# SineWaveGen.net
KiCad netlist of a schematic drawn in EAGLE
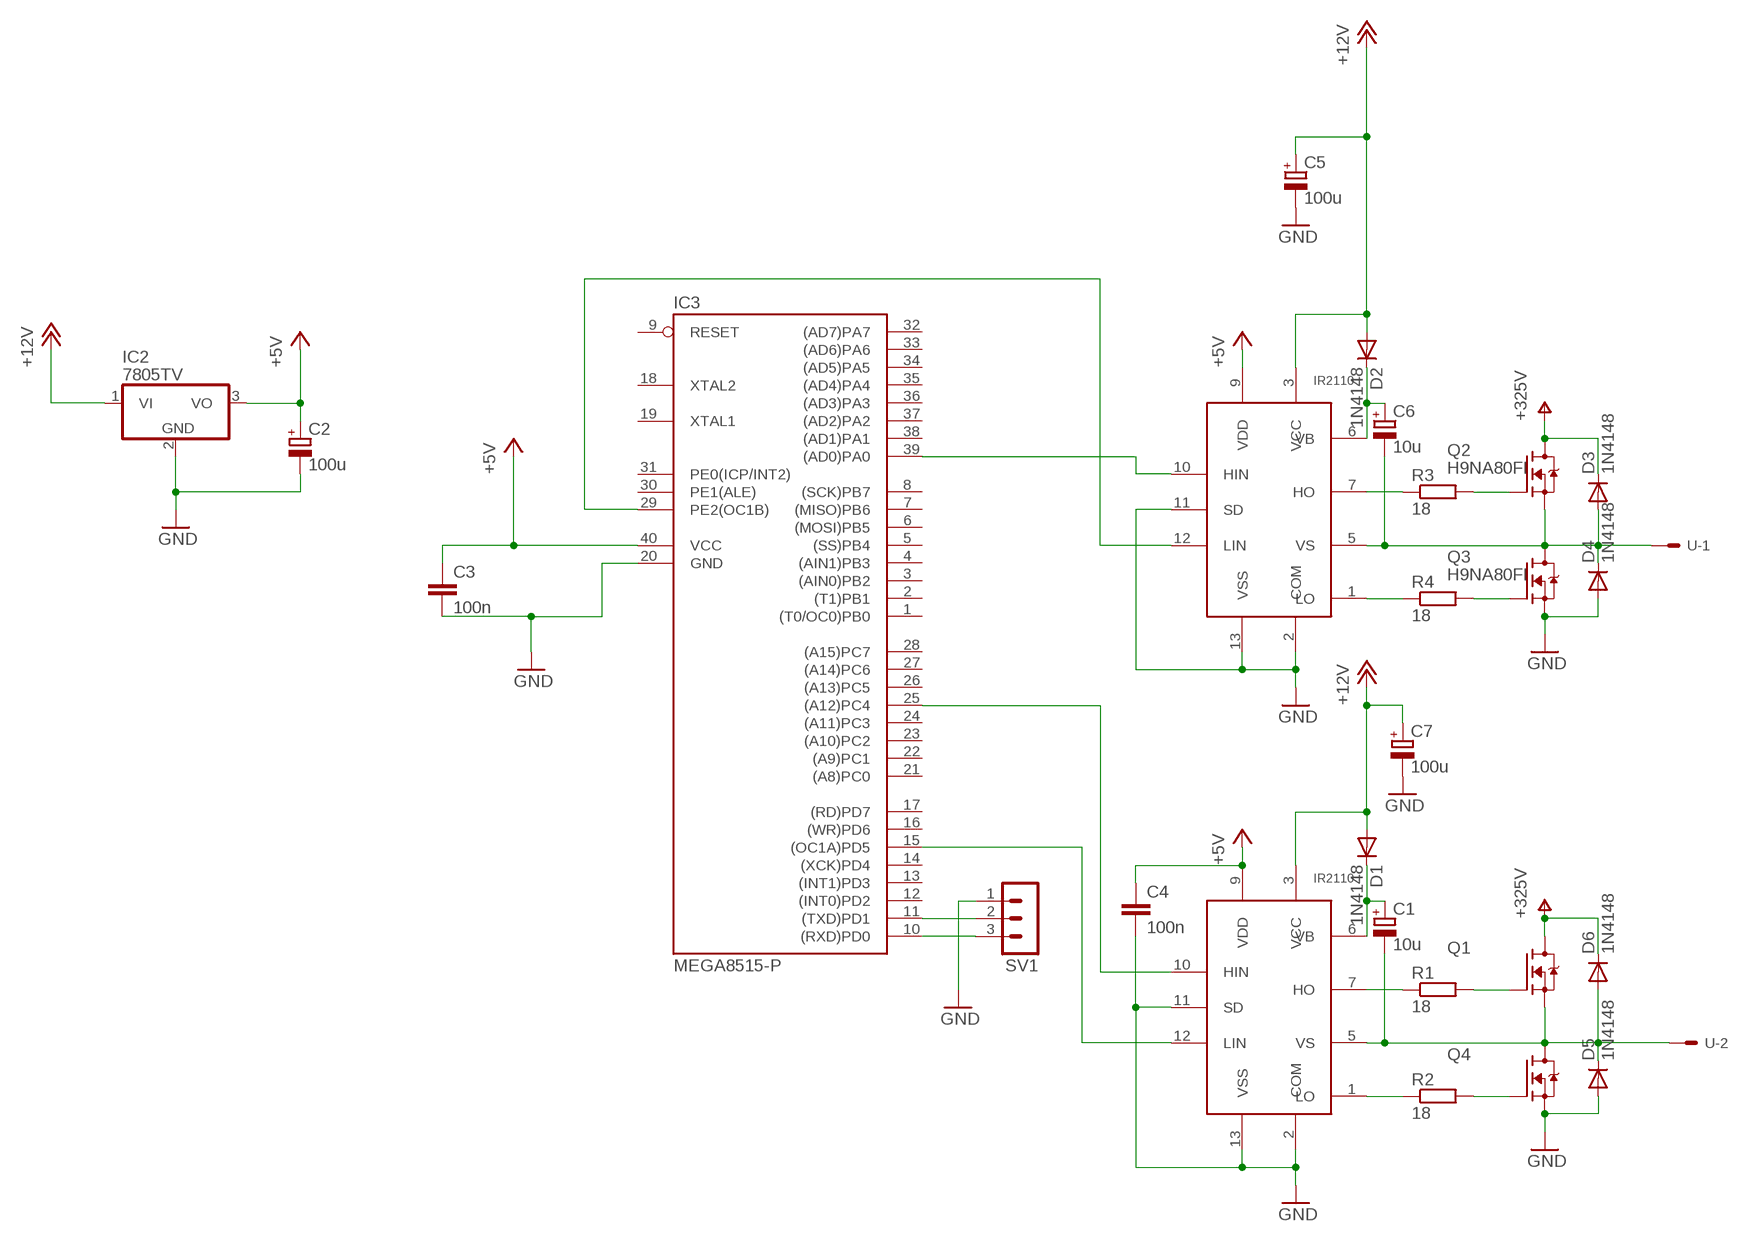
[diagram p0: schematic, sheet 1]

(export (version "E")
  (design (tool "Eeschema 10.0.6"))
  (components
    (comp (ref "C1")
      (value "10u")
      (footprint "eagle-import:E2,5-7")
      (libsource (lib "eagle-import") (part "CPOL-EUE2.5-7"))
    )
    (comp (ref "C2")
      (value "100u")
      (footprint "eagle-import:E2,5-7")
      (libsource (lib "eagle-import") (part "CPOL-EUE2.5-7"))
    )
    (comp (ref "C3")
      (value "100n")
      (footprint "eagle-import:C050-035X075")
      (libsource (lib "eagle-import") (part "C-EU050-035X075"))
    )
    (comp (ref "C4")
      (value "100n")
      (footprint "eagle-import:C050-035X075")
      (libsource (lib "eagle-import") (part "C-EU050-035X075"))
    )
    (comp (ref "C5")
      (value "100u")
      (footprint "eagle-import:E2,5-7")
      (libsource (lib "eagle-import") (part "CPOL-EUE2.5-7"))
    )
    (comp (ref "C6")
      (value "10u")
      (footprint "eagle-import:E2,5-7")
      (libsource (lib "eagle-import") (part "CPOL-EUE2.5-7"))
    )
    (comp (ref "C7")
      (value "100u")
      (footprint "eagle-import:E2,5-7")
      (libsource (lib "eagle-import") (part "CPOL-EUE2.5-7"))
    )
    (comp (ref "D1")
      (value "1N4148")
      (footprint "eagle-import:DO35-7")
      (libsource (lib "eagle-import") (part "1N4148DO35-7"))
    )
    (comp (ref "D2")
      (value "1N4148")
      (footprint "eagle-import:DO35-7")
      (libsource (lib "eagle-import") (part "1N4148DO35-7"))
    )
    (comp (ref "D3")
      (value "1N4148")
      (footprint "eagle-import:DO35-7")
      (libsource (lib "eagle-import") (part "1N4148DO35-7"))
    )
    (comp (ref "D4")
      (value "1N4148")
      (footprint "eagle-import:DO35-7")
      (libsource (lib "eagle-import") (part "1N4148DO35-7"))
    )
    (comp (ref "D5")
      (value "1N4148")
      (footprint "eagle-import:DO35-7")
      (libsource (lib "eagle-import") (part "1N4148DO35-7"))
    )
    (comp (ref "D6")
      (value "1N4148")
      (footprint "eagle-import:DO35-7")
      (libsource (lib "eagle-import") (part "1N4148DO35-7"))
    )
    (comp (ref "IC2")
      (value "7805TV")
      (footprint "eagle-import:TO220V")
      (libsource (lib "eagle-import") (part "78TV05"))
    )
    (comp (ref "IC3")
      (value "MEGA8515-P")
      (footprint "eagle-import:DIL40")
      (fields (field (name "MPN") "ATMEGA8515-16PU"))
      (libsource (lib "eagle-import") (part "MEGA8515-P"))
    )
    (comp (ref "Q1")
      (value "SPW47N60S5")
      (footprint "eagle-import:P-TO247")
      (libsource (lib "eagle-import") (part "SPW47N60S5"))
    )
    (comp (ref "Q2")
      (value "H9NA80FI")
      (footprint "eagle-import:P-TO247")
      (libsource (lib "eagle-import") (part "SPW47N60S5"))
    )
    (comp (ref "Q3")
      (value "H9NA80FI")
      (footprint "eagle-import:P-TO247")
      (libsource (lib "eagle-import") (part "SPW47N60S5"))
    )
    (comp (ref "Q4")
      (value "SPW47N60S5")
      (footprint "eagle-import:P-TO247")
      (libsource (lib "eagle-import") (part "SPW47N60S5"))
    )
    (comp (ref "R1")
      (value "18")
      (footprint "eagle-import:0207_12")
      (libsource (lib "eagle-import") (part "R-EU_0207/12"))
    )
    (comp (ref "R2")
      (value "18")
      (footprint "eagle-import:0207_12")
      (libsource (lib "eagle-import") (part "R-EU_0207/12"))
    )
    (comp (ref "R3")
      (value "18")
      (footprint "eagle-import:0207_12")
      (libsource (lib "eagle-import") (part "R-EU_0207/12"))
    )
    (comp (ref "R4")
      (value "18")
      (footprint "eagle-import:0207_12")
      (libsource (lib "eagle-import") (part "R-EU_0207/12"))
    )
    (comp (ref "SV1")
      (value "MA03-1")
      (footprint "eagle-import:MA03-1")
      (libsource (lib "eagle-import") (part "MA03-1"))
    )
    (comp (ref "U")
      (value "5566-2")
      (footprint "eagle-import:5566-2")
      (libsource (lib "eagle-import") (part "5566-2"))
    )
    (comp (ref "U$1")
      (value "IR2110")
      (footprint "eagle-import:DIL14")
      (libsource (lib "eagle-import") (part "IR2110DIL14"))
    )
    (comp (ref "U$2")
      (value "IR2110")
      (footprint "eagle-import:DIL14")
      (libsource (lib "eagle-import") (part "IR2110DIL14"))
    )
  )
  (nets
    (net (code "1") (name "+5V") (class "Default")
      (node (ref "C2") (pin "+") (pinfunction "+_+") (pintype "passive"))
      (node (ref "C3") (pin "1") (pinfunction "1_1") (pintype "passive"))
      (node (ref "C4") (pin "1") (pinfunction "1_1") (pintype "passive"))
      (node (ref "IC2") (pin "3") (pinfunction "VO_3") (pintype "passive"))
      (node (ref "IC3") (pin "40") (pinfunction "VCC_40") (pintype "power_in"))
      (node (ref "U$1") (pin "9") (pinfunction "VDD_9") (pintype "power_in"))
      (node (ref "U$2") (pin "9") (pinfunction "VDD_9") (pintype "power_in"))
    )
    (net (code "2") (name "+12V") (class "Default")
      (node (ref "C5") (pin "+") (pinfunction "+_+") (pintype "passive"))
      (node (ref "C7") (pin "+") (pinfunction "+_+") (pintype "passive"))
      (node (ref "D1") (pin "A") (pinfunction "A_A") (pintype "passive"))
      (node (ref "D2") (pin "A") (pinfunction "A_A") (pintype "passive"))
      (node (ref "IC2") (pin "1") (pinfunction "VI_1") (pintype "input"))
      (node (ref "U$1") (pin "3") (pinfunction "VCC_3") (pintype "power_in"))
      (node (ref "U$2") (pin "3") (pinfunction "VCC_3") (pintype "power_in"))
    )
    (net (code "3") (name "+325V") (class "Default")
      (node (ref "D3") (pin "C") (pinfunction "C_C") (pintype "passive"))
      (node (ref "D6") (pin "C") (pinfunction "C_C") (pintype "passive"))
      (node (ref "Q1") (pin "2") (pinfunction "D_2") (pintype "passive"))
      (node (ref "Q2") (pin "2") (pinfunction "D_2") (pintype "passive"))
    )
    (net (code "4") (name "GND") (class "Default")
      (node (ref "C2") (pin "-") (pinfunction "-_-") (pintype "passive"))
      (node (ref "C3") (pin "2") (pinfunction "2_2") (pintype "passive"))
      (node (ref "C4") (pin "2") (pinfunction "2_2") (pintype "passive"))
      (node (ref "C5") (pin "-") (pinfunction "-_-") (pintype "passive"))
      (node (ref "C7") (pin "-") (pinfunction "-_-") (pintype "passive"))
      (node (ref "D4") (pin "A") (pinfunction "A_A") (pintype "passive"))
      (node (ref "D5") (pin "A") (pinfunction "A_A") (pintype "passive"))
      (node (ref "IC2") (pin "2") (pinfunction "GND_2") (pintype "passive"))
      (node (ref "IC3") (pin "20") (pinfunction "GND_20") (pintype "power_in"))
      (node (ref "Q3") (pin "3") (pinfunction "S_3") (pintype "passive"))
      (node (ref "Q4") (pin "3") (pinfunction "S_3") (pintype "passive"))
      (node (ref "SV1") (pin "1") (pinfunction "1_1") (pintype "passive"))
      (node (ref "U$1") (pin "11") (pinfunction "SD_11") (pintype "input"))
      (node (ref "U$1") (pin "13") (pinfunction "VSS_13") (pintype "power_in"))
      (node (ref "U$1") (pin "2") (pinfunction "COM_2") (pintype "power_in"))
      (node (ref "U$2") (pin "11") (pinfunction "SD_11") (pintype "input"))
      (node (ref "U$2") (pin "13") (pinfunction "VSS_13") (pintype "power_in"))
      (node (ref "U$2") (pin "2") (pinfunction "COM_2") (pintype "power_in"))
    )
    (net (code "5") (name "Net-(IC3-(A12)PC4)") (class "Default")
      (node (ref "IC3") (pin "25") (pinfunction "(A12)PC4_25") (pintype "bidirectional"))
      (node (ref "U$1") (pin "10") (pinfunction "HIN_10") (pintype "input"))
    )
    (net (code "6") (name "Net-(IC3-(AD0)PA0)") (class "Default")
      (node (ref "IC3") (pin "39") (pinfunction "(AD0)PA0_39") (pintype "bidirectional"))
      (node (ref "U$2") (pin "10") (pinfunction "HIN_10") (pintype "input"))
    )
    (net (code "7") (name "Net-(IC3-(OC1A)PD5)") (class "Default")
      (node (ref "IC3") (pin "15") (pinfunction "(OC1A)PD5_15") (pintype "bidirectional"))
      (node (ref "U$1") (pin "12") (pinfunction "LIN_12") (pintype "input"))
    )
    (net (code "8") (name "Net-(IC3-(RXD)PD0)") (class "Default")
      (node (ref "IC3") (pin "10") (pinfunction "(RXD)PD0_10") (pintype "bidirectional"))
      (node (ref "SV1") (pin "3") (pinfunction "3_3") (pintype "passive"))
    )
    (net (code "9") (name "Net-(IC3-(TXD)PD1)") (class "Default")
      (node (ref "IC3") (pin "11") (pinfunction "(TXD)PD1_11") (pintype "bidirectional"))
      (node (ref "SV1") (pin "2") (pinfunction "2_2") (pintype "passive"))
    )
    (net (code "10") (name "Net-(IC3-PE2(OC1B))") (class "Default")
      (node (ref "IC3") (pin "29") (pinfunction "PE2(OC1B)_29") (pintype "bidirectional"))
      (node (ref "U$2") (pin "12") (pinfunction "LIN_12") (pintype "input"))
    )
    (net (code "11") (name "Net-(Q1-G)") (class "Default")
      (node (ref "Q1") (pin "1") (pinfunction "G_1") (pintype "passive"))
      (node (ref "R1") (pin "2") (pinfunction "2_2") (pintype "passive"))
    )
    (net (code "12") (name "Net-(Q1-S)") (class "Default")
      (node (ref "C1") (pin "-") (pinfunction "-_-") (pintype "passive"))
      (node (ref "D5") (pin "C") (pinfunction "C_C") (pintype "passive"))
      (node (ref "D6") (pin "A") (pinfunction "A_A") (pintype "passive"))
      (node (ref "Q1") (pin "3") (pinfunction "S_3") (pintype "passive"))
      (node (ref "Q4") (pin "2") (pinfunction "D_2") (pintype "passive"))
      (node (ref "U") (pin "2") (pinfunction "S_2") (pintype "passive"))
      (node (ref "U$1") (pin "5") (pinfunction "VS_5") (pintype "output"))
    )
    (net (code "13") (name "Net-(Q2-G)") (class "Default")
      (node (ref "Q2") (pin "1") (pinfunction "G_1") (pintype "passive"))
      (node (ref "R3") (pin "2") (pinfunction "2_2") (pintype "passive"))
    )
    (net (code "14") (name "Net-(Q2-S)") (class "Default")
      (node (ref "C6") (pin "-") (pinfunction "-_-") (pintype "passive"))
      (node (ref "D3") (pin "A") (pinfunction "A_A") (pintype "passive"))
      (node (ref "D4") (pin "C") (pinfunction "C_C") (pintype "passive"))
      (node (ref "Q2") (pin "3") (pinfunction "S_3") (pintype "passive"))
      (node (ref "Q3") (pin "2") (pinfunction "D_2") (pintype "passive"))
      (node (ref "U") (pin "1") (pinfunction "S_1") (pintype "passive"))
      (node (ref "U$2") (pin "5") (pinfunction "VS_5") (pintype "output"))
    )
    (net (code "15") (name "Net-(Q3-G)") (class "Default")
      (node (ref "Q3") (pin "1") (pinfunction "G_1") (pintype "passive"))
      (node (ref "R4") (pin "2") (pinfunction "2_2") (pintype "passive"))
    )
    (net (code "16") (name "Net-(Q4-G)") (class "Default")
      (node (ref "Q4") (pin "1") (pinfunction "G_1") (pintype "passive"))
      (node (ref "R2") (pin "2") (pinfunction "2_2") (pintype "passive"))
    )
    (net (code "17") (name "Net-(U$1-HO)") (class "Default")
      (node (ref "R1") (pin "1") (pinfunction "1_1") (pintype "passive"))
      (node (ref "U$1") (pin "7") (pinfunction "HO_7") (pintype "output"))
    )
    (net (code "18") (name "Net-(U$1-LO)") (class "Default")
      (node (ref "R2") (pin "1") (pinfunction "1_1") (pintype "passive"))
      (node (ref "U$1") (pin "1") (pinfunction "LO_1") (pintype "output"))
    )
    (net (code "19") (name "Net-(U$1-VB)") (class "Default")
      (node (ref "C1") (pin "+") (pinfunction "+_+") (pintype "passive"))
      (node (ref "D1") (pin "C") (pinfunction "C_C") (pintype "passive"))
      (node (ref "U$1") (pin "6") (pinfunction "VB_6") (pintype "power_in"))
    )
    (net (code "20") (name "Net-(U$2-HO)") (class "Default")
      (node (ref "R3") (pin "1") (pinfunction "1_1") (pintype "passive"))
      (node (ref "U$2") (pin "7") (pinfunction "HO_7") (pintype "output"))
    )
    (net (code "21") (name "Net-(U$2-LO)") (class "Default")
      (node (ref "R4") (pin "1") (pinfunction "1_1") (pintype "passive"))
      (node (ref "U$2") (pin "1") (pinfunction "LO_1") (pintype "output"))
    )
    (net (code "22") (name "Net-(U$2-VB)") (class "Default")
      (node (ref "C6") (pin "+") (pinfunction "+_+") (pintype "passive"))
      (node (ref "D2") (pin "C") (pinfunction "C_C") (pintype "passive"))
      (node (ref "U$2") (pin "6") (pinfunction "VB_6") (pintype "power_in"))
    )
    (net (code "23") (name "unconnected-(IC3-(A8)PC0-Pad21)") (class "Default")
      (node (ref "IC3") (pin "21") (pinfunction "(A8)PC0_21") (pintype "bidirectional"))
    )
    (net (code "24") (name "unconnected-(IC3-(A9)PC1-Pad22)") (class "Default")
      (node (ref "IC3") (pin "22") (pinfunction "(A9)PC1_22") (pintype "bidirectional"))
    )
    (net (code "25") (name "unconnected-(IC3-(A10)PC2-Pad23)") (class "Default")
      (node (ref "IC3") (pin "23") (pinfunction "(A10)PC2_23") (pintype "bidirectional"))
    )
    (net (code "26") (name "unconnected-(IC3-(A11)PC3-Pad24)") (class "Default")
      (node (ref "IC3") (pin "24") (pinfunction "(A11)PC3_24") (pintype "bidirectional"))
    )
    (net (code "27") (name "unconnected-(IC3-(A13)PC5-Pad26)") (class "Default")
      (node (ref "IC3") (pin "26") (pinfunction "(A13)PC5_26") (pintype "bidirectional"))
    )
    (net (code "28") (name "unconnected-(IC3-(A14)PC6-Pad27)") (class "Default")
      (node (ref "IC3") (pin "27") (pinfunction "(A14)PC6_27") (pintype "bidirectional"))
    )
    (net (code "29") (name "unconnected-(IC3-(A15)PC7-Pad28)") (class "Default")
      (node (ref "IC3") (pin "28") (pinfunction "(A15)PC7_28") (pintype "bidirectional"))
    )
    (net (code "30") (name "unconnected-(IC3-(AD1)PA1-Pad38)") (class "Default")
      (node (ref "IC3") (pin "38") (pinfunction "(AD1)PA1_38") (pintype "bidirectional"))
    )
    (net (code "31") (name "unconnected-(IC3-(AD2)PA2-Pad37)") (class "Default")
      (node (ref "IC3") (pin "37") (pinfunction "(AD2)PA2_37") (pintype "bidirectional"))
    )
    (net (code "32") (name "unconnected-(IC3-(AD3)PA3-Pad36)") (class "Default")
      (node (ref "IC3") (pin "36") (pinfunction "(AD3)PA3_36") (pintype "bidirectional"))
    )
    (net (code "33") (name "unconnected-(IC3-(AD4)PA4-Pad35)") (class "Default")
      (node (ref "IC3") (pin "35") (pinfunction "(AD4)PA4_35") (pintype "bidirectional"))
    )
    (net (code "34") (name "unconnected-(IC3-(AD5)PA5-Pad34)") (class "Default")
      (node (ref "IC3") (pin "34") (pinfunction "(AD5)PA5_34") (pintype "bidirectional"))
    )
    (net (code "35") (name "unconnected-(IC3-(AD6)PA6-Pad33)") (class "Default")
      (node (ref "IC3") (pin "33") (pinfunction "(AD6)PA6_33") (pintype "bidirectional"))
    )
    (net (code "36") (name "unconnected-(IC3-(AD7)PA7-Pad32)") (class "Default")
      (node (ref "IC3") (pin "32") (pinfunction "(AD7)PA7_32") (pintype "bidirectional"))
    )
    (net (code "37") (name "unconnected-(IC3-(AIN0)PB2-Pad3)") (class "Default")
      (node (ref "IC3") (pin "3") (pinfunction "(AIN0)PB2_3") (pintype "bidirectional"))
    )
    (net (code "38") (name "unconnected-(IC3-(AIN1)PB3-Pad4)") (class "Default")
      (node (ref "IC3") (pin "4") (pinfunction "(AIN1)PB3_4") (pintype "bidirectional"))
    )
    (net (code "39") (name "unconnected-(IC3-(INT0)PD2-Pad12)") (class "Default")
      (node (ref "IC3") (pin "12") (pinfunction "(INT0)PD2_12") (pintype "bidirectional"))
    )
    (net (code "40") (name "unconnected-(IC3-(INT1)PD3-Pad13)") (class "Default")
      (node (ref "IC3") (pin "13") (pinfunction "(INT1)PD3_13") (pintype "bidirectional"))
    )
    (net (code "41") (name "unconnected-(IC3-(MISO)PB6-Pad7)") (class "Default")
      (node (ref "IC3") (pin "7") (pinfunction "(MISO)PB6_7") (pintype "bidirectional"))
    )
    (net (code "42") (name "unconnected-(IC3-(MOSI)PB5-Pad6)") (class "Default")
      (node (ref "IC3") (pin "6") (pinfunction "(MOSI)PB5_6") (pintype "bidirectional"))
    )
    (net (code "43") (name "unconnected-(IC3-(RD)PD7-Pad17)") (class "Default")
      (node (ref "IC3") (pin "17") (pinfunction "(RD)PD7_17") (pintype "bidirectional"))
    )
    (net (code "44") (name "unconnected-(IC3-(SCK)PB7-Pad8)") (class "Default")
      (node (ref "IC3") (pin "8") (pinfunction "(SCK)PB7_8") (pintype "bidirectional"))
    )
    (net (code "45") (name "unconnected-(IC3-(SS)PB4-Pad5)") (class "Default")
      (node (ref "IC3") (pin "5") (pinfunction "(SS)PB4_5") (pintype "bidirectional"))
    )
    (net (code "46") (name "unconnected-(IC3-(T0{slash}OC0)PB0-Pad1)") (class "Default")
      (node (ref "IC3") (pin "1") (pinfunction "(T0/OC0)PB0_1") (pintype "bidirectional"))
    )
    (net (code "47") (name "unconnected-(IC3-(T1)PB1-Pad2)") (class "Default")
      (node (ref "IC3") (pin "2") (pinfunction "(T1)PB1_2") (pintype "bidirectional"))
    )
    (net (code "48") (name "unconnected-(IC3-(WR)PD6-Pad16)") (class "Default")
      (node (ref "IC3") (pin "16") (pinfunction "(WR)PD6_16") (pintype "bidirectional"))
    )
    (net (code "49") (name "unconnected-(IC3-(XCK)PD4-Pad14)") (class "Default")
      (node (ref "IC3") (pin "14") (pinfunction "(XCK)PD4_14") (pintype "bidirectional"))
    )
    (net (code "50") (name "unconnected-(IC3-PE0(ICP{slash}INT2)-Pad31)") (class "Default")
      (node (ref "IC3") (pin "31") (pinfunction "PE0(ICP/INT2)_31") (pintype "bidirectional"))
    )
    (net (code "51") (name "unconnected-(IC3-PE1(ALE)-Pad30)") (class "Default")
      (node (ref "IC3") (pin "30") (pinfunction "PE1(ALE)_30") (pintype "bidirectional"))
    )
    (net (code "52") (name "unconnected-(IC3-RESET-Pad9)") (class "Default")
      (node (ref "IC3") (pin "9") (pinfunction "RESET_9") (pintype "input"))
    )
    (net (code "53") (name "unconnected-(IC3-XTAL1-Pad19)") (class "Default")
      (node (ref "IC3") (pin "19") (pinfunction "XTAL1_19") (pintype "bidirectional"))
    )
    (net (code "54") (name "unconnected-(IC3-XTAL2-Pad18)") (class "Default")
      (node (ref "IC3") (pin "18") (pinfunction "XTAL2_18") (pintype "bidirectional"))
    )
  )
)
